# esc_ne5551.net
KiCad netlist of a schematic drawn in EAGLE
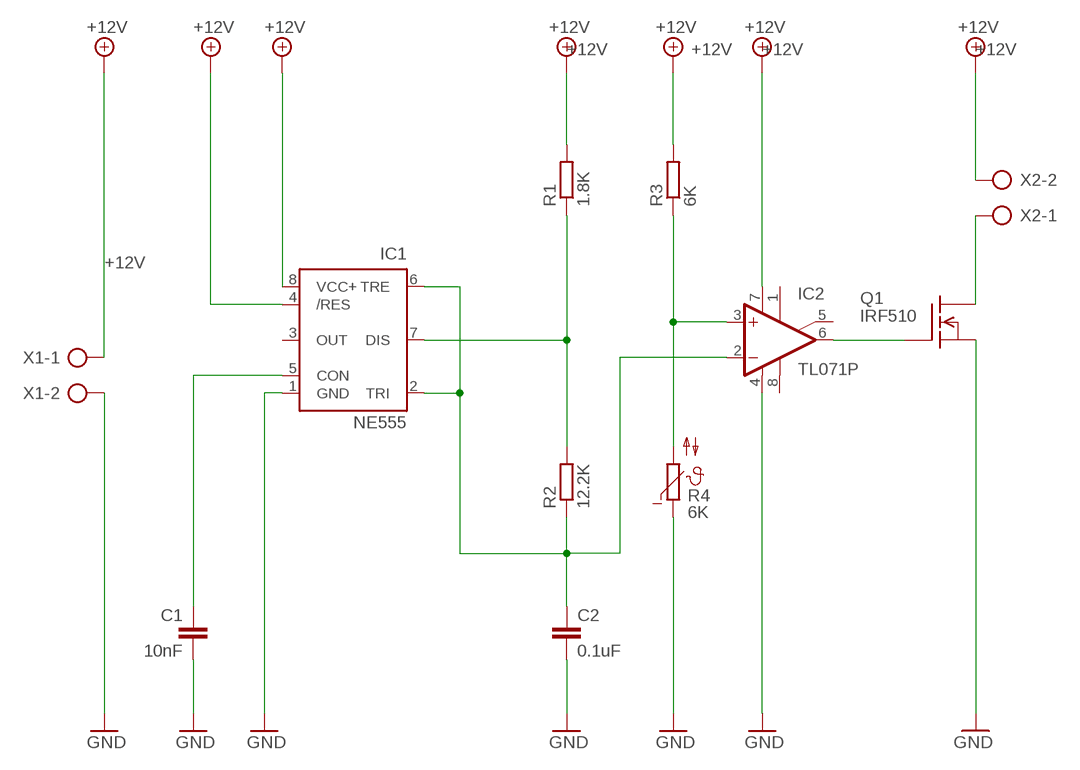
[diagram p0: schematic, sheet 1]

(export (version "E")
  (design (tool "Eeschema 10.0.6"))
  (components
    (comp (ref "C1")
      (value "10nF")
      (footprint "eagle-import:C025-025X050")
      (libsource (lib "eagle-import") (part "C-EU025-025X050"))
    )
    (comp (ref "C2")
      (value "0.1uF")
      (footprint "eagle-import:C025-025X050")
      (libsource (lib "eagle-import") (part "C-EU025-025X050"))
    )
    (comp (ref "IC1")
      (value "NE555")
      (footprint "eagle-import:DIL-08")
      (fields (field (name "MF") "Arrow Electronics") (field (name "MPN") "NE555N"))
      (libsource (lib "eagle-import") (part "NE555"))
    )
    (comp (ref "IC2")
      (value "TL071P")
      (footprint "eagle-import:DIL08")
      (libsource (lib "eagle-import") (part "TL071P"))
    )
    (comp (ref "Q1")
      (value "IRF510")
      (footprint "eagle-import:TO220")
      (libsource (lib "eagle-import") (part "IRF510"))
    )
    (comp (ref "R1")
      (value "1.8K")
      (footprint "eagle-import:0207_10")
      (libsource (lib "eagle-import") (part "R-EU_0207/10"))
    )
    (comp (ref "R2")
      (value "12.2K")
      (footprint "eagle-import:0207_10")
      (libsource (lib "eagle-import") (part "R-EU_0207/10"))
    )
    (comp (ref "R3")
      (value "6K")
      (footprint "eagle-import:0207_10")
      (libsource (lib "eagle-import") (part "R-EU_0207/10"))
    )
    (comp (ref "R4")
      (value "6K")
      (footprint "eagle-import:P640")
      (libsource (lib "eagle-import") (part "NTC640"))
    )
    (comp (ref "X1")
      (value "AK500/2")
      (footprint "eagle-import:AK500_2")
      (libsource (lib "eagle-import") (part "AK500/2"))
    )
    (comp (ref "X2")
      (value "AK500/2")
      (footprint "eagle-import:AK500_2")
      (libsource (lib "eagle-import") (part "AK500/2"))
    )
  )
  (nets
    (net (code "1") (name "+12V") (class "Default")
      (node (ref "IC1") (pin "4") (pinfunction "/RES_4") (pintype "input"))
      (node (ref "IC1") (pin "8") (pinfunction "VCC+_8") (pintype "power_in"))
      (node (ref "IC2") (pin "7") (pinfunction "V+_7") (pintype "power_in"))
      (node (ref "R1") (pin "2") (pinfunction "2_2") (pintype "passive"))
      (node (ref "R3") (pin "2") (pinfunction "2_2") (pintype "passive"))
      (node (ref "X1") (pin "1") (pinfunction "KL_1") (pintype "passive"))
      (node (ref "X2") (pin "2") (pinfunction "KL_2") (pintype "passive"))
    )
    (net (code "2") (name "GND") (class "Default")
      (node (ref "C1") (pin "2") (pinfunction "2_2") (pintype "passive"))
      (node (ref "C2") (pin "2") (pinfunction "2_2") (pintype "passive"))
      (node (ref "IC1") (pin "1") (pinfunction "GND_1") (pintype "power_in"))
      (node (ref "IC2") (pin "4") (pinfunction "V-_4") (pintype "power_in"))
      (node (ref "Q1") (pin "3") (pinfunction "S_3") (pintype "passive"))
      (node (ref "R4") (pin "1") (pinfunction "1_1") (pintype "passive"))
      (node (ref "X1") (pin "2") (pinfunction "KL_2") (pintype "passive"))
    )
    (net (code "3") (name "Net-(IC1-CON)") (class "Default")
      (node (ref "C1") (pin "1") (pinfunction "1_1") (pintype "passive"))
      (node (ref "IC1") (pin "5") (pinfunction "CON_5") (pintype "input"))
    )
    (net (code "4") (name "Net-(IC1-DIS)") (class "Default")
      (node (ref "IC1") (pin "7") (pinfunction "DIS_7") (pintype "input"))
      (node (ref "R1") (pin "1") (pinfunction "1_1") (pintype "passive"))
      (node (ref "R2") (pin "2") (pinfunction "2_2") (pintype "passive"))
    )
    (net (code "5") (name "Net-(IC1-TRE)") (class "Default")
      (node (ref "C2") (pin "1") (pinfunction "1_1") (pintype "passive"))
      (node (ref "IC1") (pin "2") (pinfunction "TRI_2") (pintype "input"))
      (node (ref "IC1") (pin "6") (pinfunction "TRE_6") (pintype "input"))
      (node (ref "IC2") (pin "2") (pinfunction "-IN_2") (pintype "input"))
      (node (ref "R2") (pin "1") (pinfunction "1_1") (pintype "passive"))
    )
    (net (code "6") (name "Net-(IC2-+IN)") (class "Default")
      (node (ref "IC2") (pin "3") (pinfunction "+IN_3") (pintype "input"))
      (node (ref "R3") (pin "1") (pinfunction "1_1") (pintype "passive"))
      (node (ref "R4") (pin "2") (pinfunction "2_2") (pintype "passive"))
    )
    (net (code "7") (name "Net-(IC2-OUT)") (class "Default")
      (node (ref "IC2") (pin "6") (pinfunction "OUT_6") (pintype "output"))
      (node (ref "Q1") (pin "1") (pinfunction "G_1") (pintype "passive"))
    )
    (net (code "8") (name "Net-(Q1-D)") (class "Default")
      (node (ref "Q1") (pin "2") (pinfunction "D_2") (pintype "passive"))
      (node (ref "X2") (pin "1") (pinfunction "KL_1") (pintype "passive"))
    )
    (net (code "9") (name "unconnected-(IC1-OUT-Pad3)") (class "Default")
      (node (ref "IC1") (pin "3") (pinfunction "OUT_3") (pintype "output"))
    )
    (net (code "10") (name "unconnected-(IC2-ON1-Pad1)") (class "Default")
      (node (ref "IC2") (pin "1") (pinfunction "ON1_1") (pintype "passive"))
    )
    (net (code "11") (name "unconnected-(IC2-ON2-Pad5)") (class "Default")
      (node (ref "IC2") (pin "5") (pinfunction "ON2_5") (pintype "passive"))
    )
    (net (code "12") (name "unconnected-(IC2-OPT-Pad8)") (class "Default")
      (node (ref "IC2") (pin "8") (pinfunction "OPT_8") (pintype "passive"))
    )
  )
)
